# mosfet_ver2.net
KiCad netlist of a schematic drawn in EAGLE
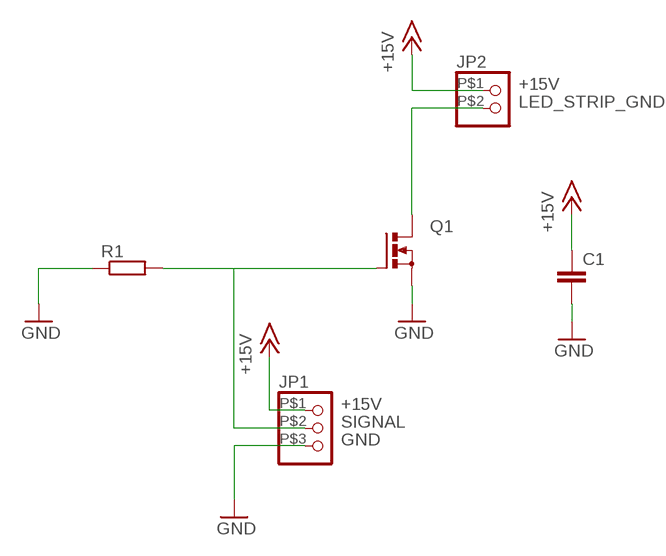
[diagram p0: schematic, sheet 1]

(export (version "E")
  (design (tool "Eeschema 10.0.6"))
  (components
    (comp (ref "C1")
      (value "C-EU050-025X075")
      (footprint "eagle-import:C050-025X075")
      (libsource (lib "eagle-import") (part "C-EU050-025X075"))
    )
    (comp (ref "JP1")
      (value "PINHD-1X35.08")
      (footprint "eagle-import:1X03_5.08")
      (libsource (lib "eagle-import") (part "PINHD-1X35.08"))
    )
    (comp (ref "JP2")
      (value "PINHD-1X2/5.08")
      (footprint "eagle-import:1X02_5.08")
      (libsource (lib "eagle-import") (part "PINHD-1X2/5.08"))
    )
    (comp (ref "Q1")
      (value "PMOSFET_NTO220BV")
      (footprint "eagle-import:TO220BV")
      (libsource (lib "eagle-import") (part "PMOSFET_NTO220BV"))
    )
    (comp (ref "R1")
      (value "R-EU_M0805")
      (footprint "eagle-import:M0805")
      (libsource (lib "eagle-import") (part "R-EU_M0805"))
    )
  )
  (nets
    (net (code "1") (name "+15V") (class "Default")
      (node (ref "C1") (pin "1") (pinfunction "1_1") (pintype "passive"))
      (node (ref "JP1") (pin "P$1") (pinfunction "1_P$1") (pintype "passive"))
      (node (ref "JP2") (pin "P$1") (pinfunction "1_P$1") (pintype "passive"))
    )
    (net (code "2") (name "/LED_STRIP_GND") (class "Default")
      (node (ref "JP2") (pin "P$2") (pinfunction "2_P$2") (pintype "passive"))
      (node (ref "Q1") (pin "D") (pinfunction "D_D") (pintype "passive"))
    )
    (net (code "3") (name "/SIGNAL") (class "Default")
      (node (ref "JP1") (pin "P$2") (pinfunction "2_P$2") (pintype "passive"))
      (node (ref "Q1") (pin "G") (pinfunction "G_G") (pintype "passive"))
      (node (ref "R1") (pin "2") (pinfunction "2_2") (pintype "passive"))
    )
    (net (code "4") (name "GND") (class "Default")
      (node (ref "C1") (pin "2") (pinfunction "2_2") (pintype "passive"))
      (node (ref "JP1") (pin "P$3") (pinfunction "3_P$3") (pintype "passive"))
      (node (ref "Q1") (pin "S") (pinfunction "S_S") (pintype "passive"))
      (node (ref "R1") (pin "1") (pinfunction "1_1") (pintype "passive"))
    )
  )
)
